# T-FLASH.net
KiCad netlist of a schematic drawn in Altium Designer
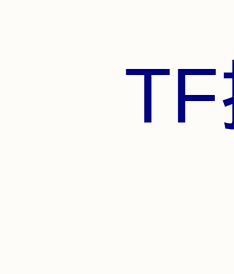
[diagram p0: T-FLASH.SchDoc, top left]
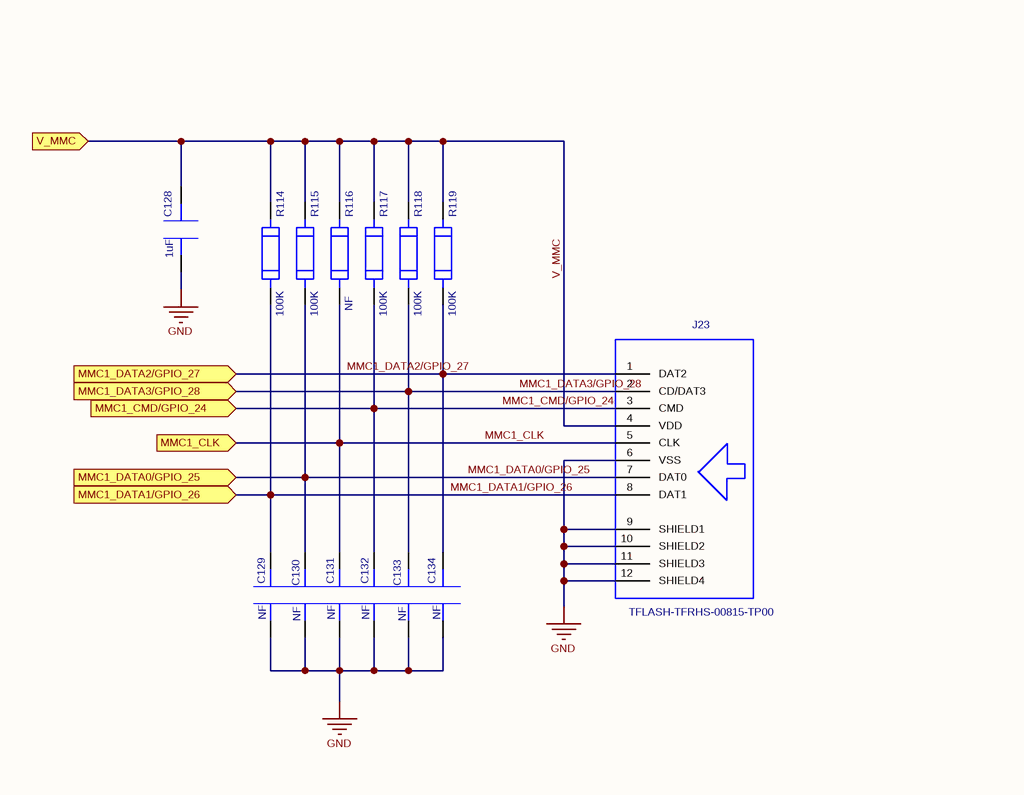
[diagram p1: T-FLASH.SchDoc, top middle]
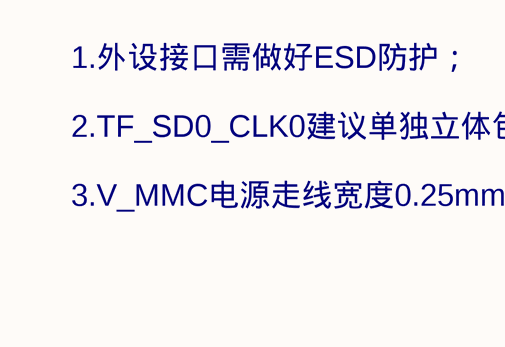
[diagram p2: T-FLASH.SchDoc, bottom middle]
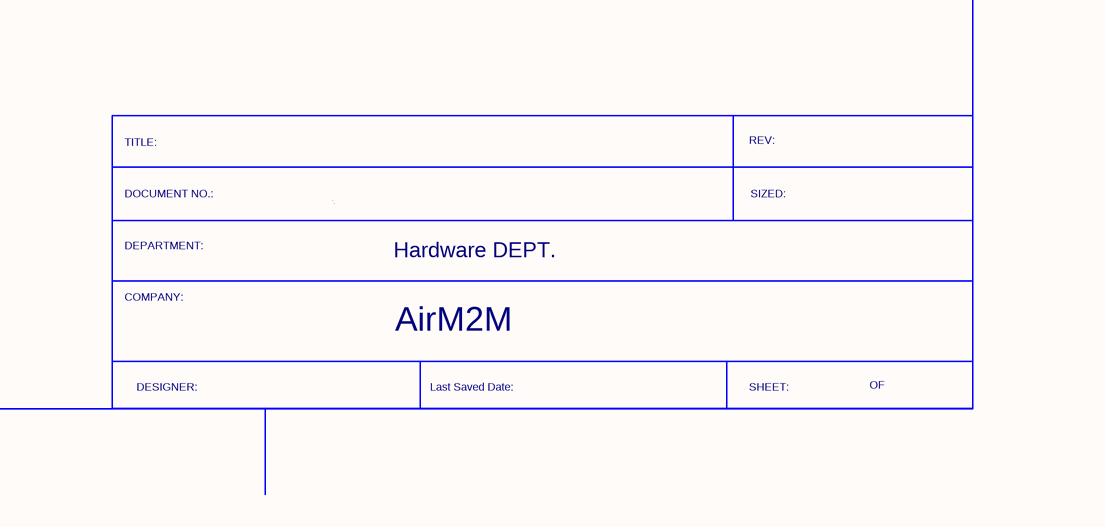
[diagram p3: T-FLASH.SchDoc, bottom right]

(export (version "E")
  (design (tool "Eeschema 10.0.6"))
  (components
    (comp (ref "C128")
      (value "1uF")
      (footprint "SC0402")
      (description "CAP CER X5R;1uF;+/-10%;6.3V;0402;0.5mm;ROHS")
      (fields (field (name "TOLERANCE") "+/-10%") (field (name "Comment") "CAP-1UF-0402-X5R"))
      (libsource (lib "*") (part "CAP-1UF-0402-X5R"))
    )
    (comp (ref "C129")
      (value "NF")
      (footprint "SC0402-NF")
      (fields (field (name "Comment") "CAP-0402-NF"))
      (libsource (lib "*") (part "CAP-0402-NF"))
    )
    (comp (ref "C130")
      (value "NF")
      (footprint "SC0402-NF")
      (fields (field (name "Comment") "CAP-0402-NF"))
      (libsource (lib "*") (part "CAP-0402-NF"))
    )
    (comp (ref "C131")
      (value "NF")
      (footprint "SC0402-NF")
      (fields (field (name "Comment") "CAP-0402-NF"))
      (libsource (lib "*") (part "CAP-0402-NF"))
    )
    (comp (ref "C132")
      (value "NF")
      (footprint "SC0402-NF")
      (fields (field (name "Comment") "CAP-0402-NF"))
      (libsource (lib "*") (part "CAP-0402-NF"))
    )
    (comp (ref "C133")
      (value "NF")
      (footprint "SC0402-NF")
      (fields (field (name "Comment") "CAP-0402-NF"))
      (libsource (lib "*") (part "CAP-0402-NF"))
    )
    (comp (ref "C134")
      (value "NF")
      (footprint "SC0402-NF")
      (fields (field (name "Comment") "CAP-0402-NF"))
      (libsource (lib "*") (part "CAP-0402-NF"))
    )
    (comp (ref "J23")
      (value "TFLASH-TFRHS-00815-TP00")
      (footprint "TFLASH-TFRHS-00815-TP00")
      (description "T-FLASH卡座;8PIN;掀盖式;13.6*14.5*1.95mm;ROHS")
      (libsource (lib "*") (part "TFLASH-TFRHS-00815-TP00"))
    )
    (comp (ref "R114")
      (value "100K")
      (footprint "SR0402")
      (description "RES FILM;100K;+/-5%;1/16W;0402;0.4mm;ROHS")
      (fields (field (name "TOLERANCE") "+/-5%") (field (name "Comment") "RES-100K-0402"))
      (libsource (lib "*") (part "RES-100K-0402"))
    )
    (comp (ref "R115")
      (value "100K")
      (footprint "SR0402")
      (description "RES FILM;100K;+/-5%;1/16W;0402;0.4mm;ROHS")
      (fields (field (name "TOLERANCE") "+/-5%") (field (name "Comment") "RES-100K-0402"))
      (libsource (lib "*") (part "RES-100K-0402"))
    )
    (comp (ref "R116")
      (value "NF")
      (footprint "SR0402-NF")
      (fields (field (name "TOLERANCE") "+/-5%") (field (name "Comment") "RES-0402-NF"))
      (libsource (lib "*") (part "RES-0402-NF"))
    )
    (comp (ref "R117")
      (value "100K")
      (footprint "SR0402")
      (description "RES FILM;100K;+/-5%;1/16W;0402;0.4mm;ROHS")
      (fields (field (name "TOLERANCE") "+/-5%") (field (name "Comment") "RES-100K-0402"))
      (libsource (lib "*") (part "RES-100K-0402"))
    )
    (comp (ref "R118")
      (value "100K")
      (footprint "SR0402")
      (description "RES FILM;100K;+/-5%;1/16W;0402;0.4mm;ROHS")
      (fields (field (name "TOLERANCE") "+/-5%") (field (name "Comment") "RES-100K-0402"))
      (libsource (lib "*") (part "RES-100K-0402"))
    )
    (comp (ref "R119")
      (value "100K")
      (footprint "SR0402")
      (description "RES FILM;100K;+/-5%;1/16W;0402;0.4mm;ROHS")
      (fields (field (name "TOLERANCE") "+/-5%") (field (name "Comment") "RES-100K-0402"))
      (libsource (lib "*") (part "RES-100K-0402"))
    )
  )
  (nets
    (net (code "1") (name "/MMC1_CLK") (class "Default")
      (node (ref "C131") (pin "1") (pinfunction "1_1") (pintype "passive"))
      (node (ref "J23") (pin "5") (pinfunction "CLK_5") (pintype "passive"))
      (node (ref "R116") (pin "1") (pinfunction "1_1") (pintype "passive"))
    )
    (net (code "2") (name "/MMC1_CMD{slash}GPIO_24") (class "Default")
      (node (ref "C132") (pin "1") (pinfunction "1_1") (pintype "passive"))
      (node (ref "J23") (pin "3") (pinfunction "CMD_3") (pintype "passive"))
      (node (ref "R117") (pin "1") (pinfunction "1_1") (pintype "passive"))
    )
    (net (code "3") (name "/MMC1_DATA0{slash}GPIO_25") (class "Default")
      (node (ref "C130") (pin "1") (pinfunction "1_1") (pintype "passive"))
      (node (ref "J23") (pin "7") (pinfunction "DAT0_7") (pintype "passive"))
      (node (ref "R115") (pin "1") (pinfunction "1_1") (pintype "passive"))
    )
    (net (code "4") (name "/MMC1_DATA1{slash}GPIO_26") (class "Default")
      (node (ref "C129") (pin "1") (pinfunction "1_1") (pintype "passive"))
      (node (ref "J23") (pin "8") (pinfunction "DAT1_8") (pintype "passive"))
      (node (ref "R114") (pin "1") (pinfunction "1_1") (pintype "passive"))
    )
    (net (code "5") (name "/MMC1_DATA2{slash}GPIO_27") (class "Default")
      (node (ref "C134") (pin "1") (pinfunction "1_1") (pintype "passive"))
      (node (ref "J23") (pin "1") (pinfunction "DAT2_1") (pintype "passive"))
      (node (ref "R119") (pin "1") (pinfunction "1_1") (pintype "passive"))
    )
    (net (code "6") (name "/MMC1_DATA3{slash}GPIO_28") (class "Default")
      (node (ref "C133") (pin "1") (pinfunction "1_1") (pintype "passive"))
      (node (ref "J23") (pin "2") (pinfunction "CD/DAT3_2") (pintype "passive"))
      (node (ref "R118") (pin "1") (pinfunction "1_1") (pintype "passive"))
    )
    (net (code "7") (name "/V_MMC") (class "Default")
      (node (ref "C128") (pin "1") (pinfunction "1_1") (pintype "passive"))
      (node (ref "J23") (pin "4") (pinfunction "VDD_4") (pintype "passive"))
      (node (ref "R114") (pin "2") (pinfunction "2_2") (pintype "passive"))
      (node (ref "R115") (pin "2") (pinfunction "2_2") (pintype "passive"))
      (node (ref "R116") (pin "2") (pinfunction "2_2") (pintype "passive"))
      (node (ref "R117") (pin "2") (pinfunction "2_2") (pintype "passive"))
      (node (ref "R118") (pin "2") (pinfunction "2_2") (pintype "passive"))
      (node (ref "R119") (pin "2") (pinfunction "2_2") (pintype "passive"))
    )
    (net (code "8") (name "GND") (class "Default")
      (node (ref "C128") (pin "2") (pinfunction "2_2") (pintype "passive"))
      (node (ref "C129") (pin "2") (pinfunction "2_2") (pintype "passive"))
      (node (ref "C130") (pin "2") (pinfunction "2_2") (pintype "passive"))
      (node (ref "C131") (pin "2") (pinfunction "2_2") (pintype "passive"))
      (node (ref "C132") (pin "2") (pinfunction "2_2") (pintype "passive"))
      (node (ref "C133") (pin "2") (pinfunction "2_2") (pintype "passive"))
      (node (ref "C134") (pin "2") (pinfunction "2_2") (pintype "passive"))
      (node (ref "J23") (pin "10") (pinfunction "SHIELD2_10") (pintype "passive"))
      (node (ref "J23") (pin "11") (pinfunction "SHIELD3_11") (pintype "passive"))
      (node (ref "J23") (pin "12") (pinfunction "SHIELD4_12") (pintype "passive"))
      (node (ref "J23") (pin "6") (pinfunction "VSS_6") (pintype "passive"))
      (node (ref "J23") (pin "9") (pinfunction "SHIELD1_9") (pintype "passive"))
    )
  )
)
